# button.net
KiCad netlist of a schematic drawn in EAGLE
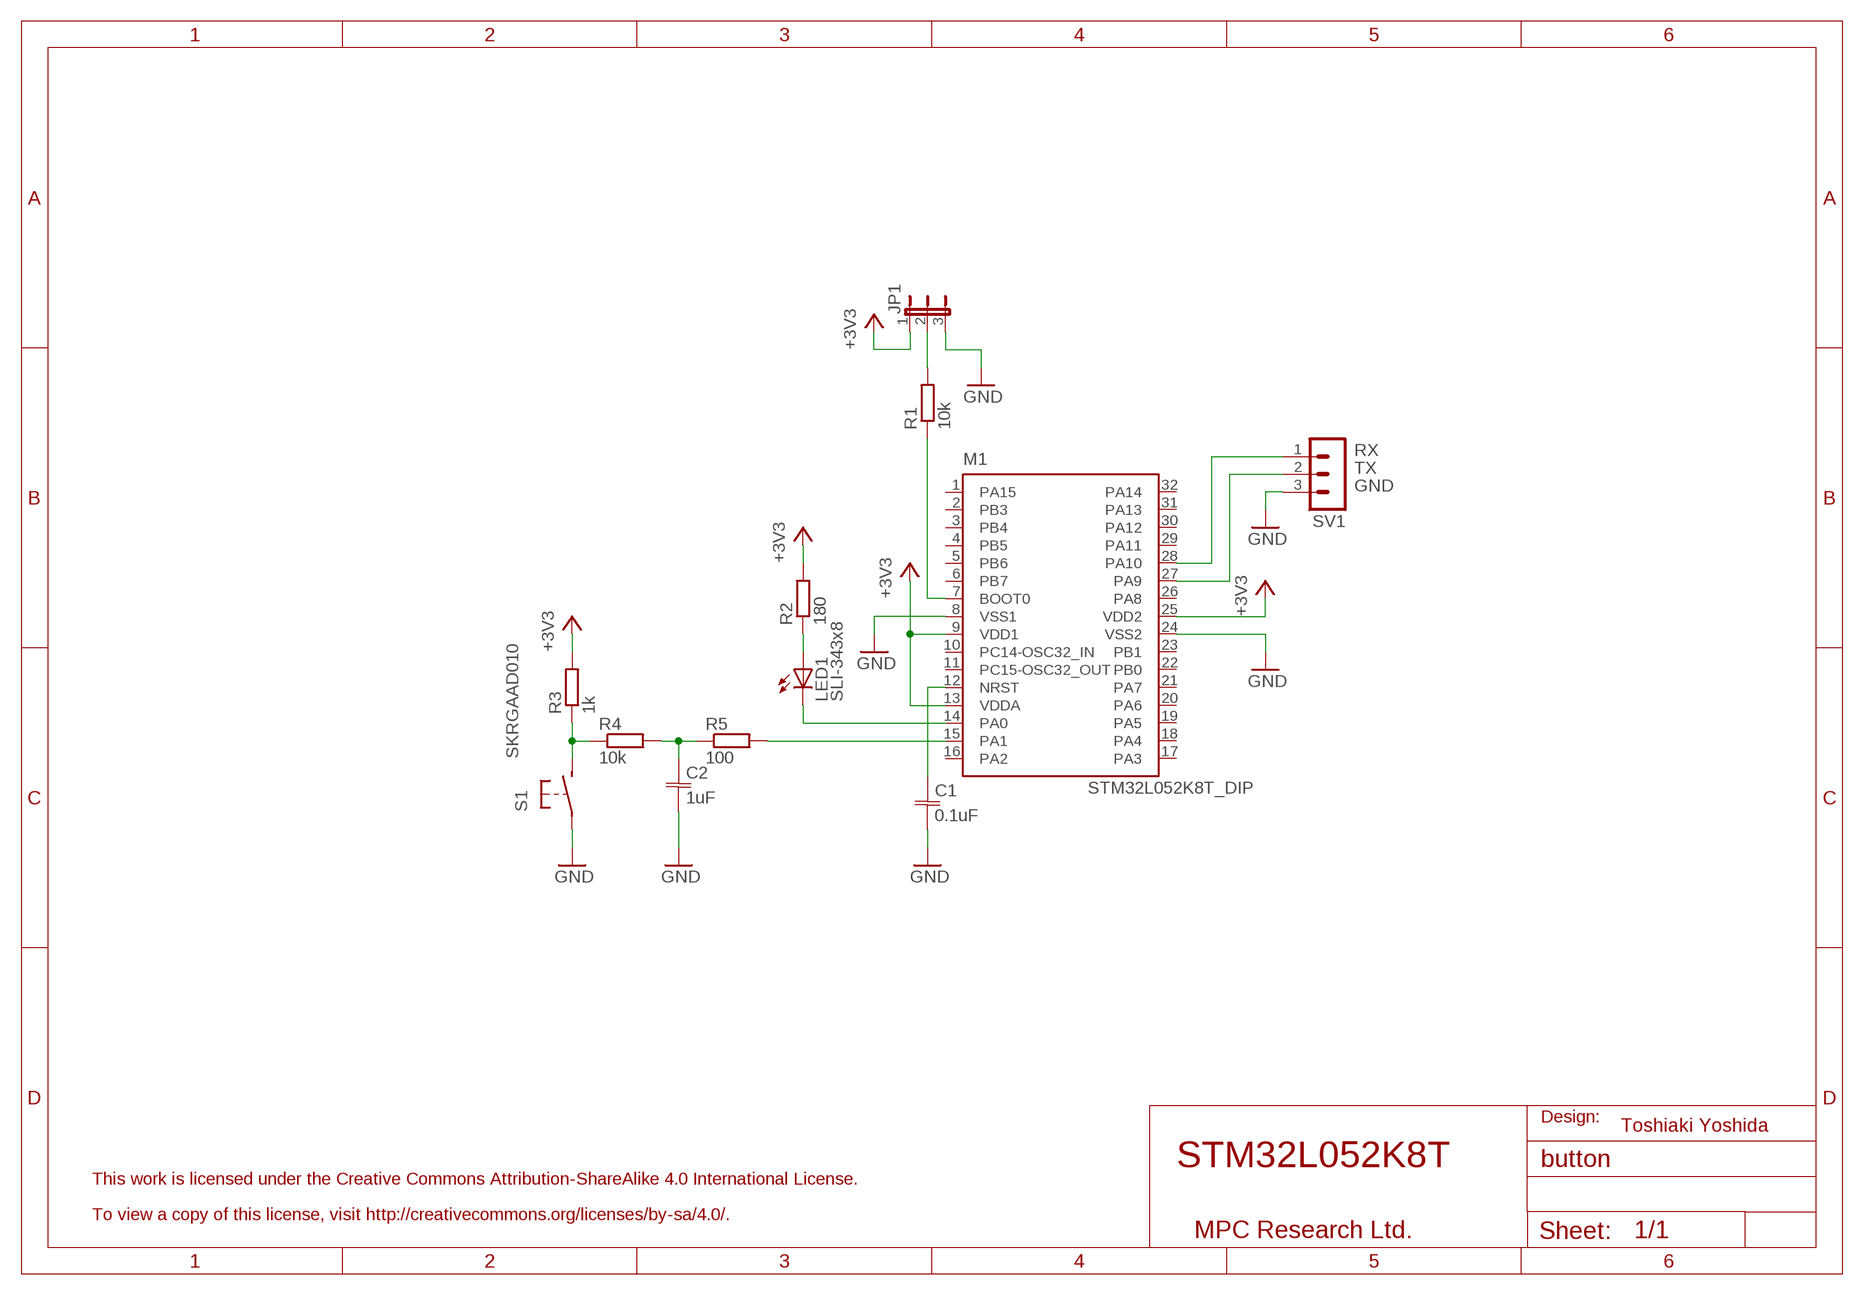
[diagram p0: schematic, sheet 1]

(export (version "E")
  (design (tool "Eeschema 10.0.6"))
  (components
    (comp (ref "C1")
      (value "0.1uF")
      (footprint "eagle-import:C050-024X044")
      (libsource (lib "eagle-import") (part "C-JIS050-024X044"))
    )
    (comp (ref "C2")
      (value "1uF")
      (footprint "eagle-import:C050-024X044")
      (libsource (lib "eagle-import") (part "C-JIS050-024X044"))
    )
    (comp (ref "JP1")
      (value "JP2E")
      (footprint "eagle-import:JP2")
      (libsource (lib "eagle-import") (part "JP2E"))
    )
    (comp (ref "LED1")
      (value "SLI-343x8")
      (footprint "eagle-import:LED3MM")
      (libsource (lib "eagle-import") (part "LED3MM"))
    )
    (comp (ref "M1")
      (value "STM32L052K8T_DIP")
      (footprint "eagle-import:DIP32")
      (libsource (lib "eagle-import") (part "STM32L052K8T_DIP"))
    )
    (comp (ref "R1")
      (value "10k")
      (footprint "eagle-import:0207_2V")
      (libsource (lib "eagle-import") (part "R-EU_0207/2V"))
    )
    (comp (ref "R2")
      (value "180")
      (footprint "eagle-import:0207_2V")
      (libsource (lib "eagle-import") (part "R-EU_0207/2V"))
    )
    (comp (ref "R3")
      (value "1k")
      (footprint "eagle-import:0207_2V")
      (libsource (lib "eagle-import") (part "R-EU_0207/2V"))
    )
    (comp (ref "R4")
      (value "10k")
      (footprint "eagle-import:0207_2V")
      (libsource (lib "eagle-import") (part "R-EU_0207/2V"))
    )
    (comp (ref "R5")
      (value "100")
      (footprint "eagle-import:0207_2V")
      (libsource (lib "eagle-import") (part "R-EU_0207/2V"))
    )
    (comp (ref "S1")
      (value "SKRGAAD010")
      (footprint "eagle-import:SKRG")
      (libsource (lib "eagle-import") (part "SKRGAAD010"))
    )
    (comp (ref "SV1")
      (value "MA03-1")
      (footprint "eagle-import:MA03-1")
      (libsource (lib "eagle-import") (part "MA03-1"))
    )
  )
  (nets
    (net (code "1") (name "+3V3") (class "Default")
      (node (ref "JP1") (pin "1") (pinfunction "1_1") (pintype "passive"))
      (node (ref "M1") (pin "13") (pinfunction "VDDA_13") (pintype "power_in"))
      (node (ref "M1") (pin "25") (pinfunction "VDD2_25") (pintype "bidirectional"))
      (node (ref "M1") (pin "9") (pinfunction "VDD1_9") (pintype "power_in"))
      (node (ref "R2") (pin "2") (pinfunction "2_2") (pintype "passive"))
      (node (ref "R3") (pin "2") (pinfunction "2_2") (pintype "passive"))
    )
    (net (code "2") (name "GND") (class "Default")
      (node (ref "C1") (pin "2") (pinfunction "2_2") (pintype "passive"))
      (node (ref "C2") (pin "2") (pinfunction "2_2") (pintype "passive"))
      (node (ref "JP1") (pin "3") (pinfunction "3_3") (pintype "passive"))
      (node (ref "M1") (pin "24") (pinfunction "VSS2_24") (pintype "power_in"))
      (node (ref "M1") (pin "8") (pinfunction "VSS1_8") (pintype "power_in"))
      (node (ref "S1") (pin "P$1") (pinfunction "1_P$1") (pintype "passive"))
      (node (ref "SV1") (pin "3") (pinfunction "3_3") (pintype "passive"))
    )
    (net (code "3") (name "Net-(C2-Pad1)") (class "Default")
      (node (ref "C2") (pin "1") (pinfunction "1_1") (pintype "passive"))
      (node (ref "R4") (pin "2") (pinfunction "2_2") (pintype "passive"))
      (node (ref "R5") (pin "1") (pinfunction "1_1") (pintype "passive"))
    )
    (net (code "4") (name "Net-(JP1-Pad2)") (class "Default")
      (node (ref "JP1") (pin "2") (pinfunction "2_2") (pintype "passive"))
      (node (ref "R1") (pin "2") (pinfunction "2_2") (pintype "passive"))
    )
    (net (code "5") (name "Net-(LED1-C)") (class "Default")
      (node (ref "LED1") (pin "K") (pinfunction "C_K") (pintype "passive"))
      (node (ref "M1") (pin "14") (pinfunction "PA0_14") (pintype "bidirectional"))
    )
    (net (code "6") (name "Net-(LED1-PadA)") (class "Default")
      (node (ref "LED1") (pin "A") (pinfunction "A_A") (pintype "passive"))
      (node (ref "R2") (pin "1") (pinfunction "1_1") (pintype "passive"))
    )
    (net (code "7") (name "Net-(M1-BOOT0)") (class "Default")
      (node (ref "M1") (pin "7") (pinfunction "BOOT0_7") (pintype "bidirectional"))
      (node (ref "R1") (pin "1") (pinfunction "1_1") (pintype "passive"))
    )
    (net (code "8") (name "Net-(M1-NRST)") (class "Default")
      (node (ref "C1") (pin "1") (pinfunction "1_1") (pintype "passive"))
      (node (ref "M1") (pin "12") (pinfunction "NRST_12") (pintype "bidirectional"))
    )
    (net (code "9") (name "Net-(M1-PA1)") (class "Default")
      (node (ref "M1") (pin "15") (pinfunction "PA1_15") (pintype "bidirectional"))
      (node (ref "R5") (pin "2") (pinfunction "2_2") (pintype "passive"))
    )
    (net (code "10") (name "Net-(M1-PA9)") (class "Default")
      (node (ref "M1") (pin "27") (pinfunction "PA9_27") (pintype "bidirectional"))
      (node (ref "SV1") (pin "2") (pinfunction "2_2") (pintype "passive"))
    )
    (net (code "11") (name "Net-(M1-PA10)") (class "Default")
      (node (ref "M1") (pin "28") (pinfunction "PA10_28") (pintype "bidirectional"))
      (node (ref "SV1") (pin "1") (pinfunction "1_1") (pintype "passive"))
    )
    (net (code "12") (name "Net-(S1-2)") (class "Default")
      (node (ref "R3") (pin "1") (pinfunction "1_1") (pintype "passive"))
      (node (ref "R4") (pin "1") (pinfunction "1_1") (pintype "passive"))
      (node (ref "S1") (pin "P$2") (pinfunction "2_P$2") (pintype "passive"))
    )
    (net (code "13") (name "unconnected-(M1-PA2-Pad16)") (class "Default")
      (node (ref "M1") (pin "16") (pinfunction "PA2_16") (pintype "bidirectional"))
    )
    (net (code "14") (name "unconnected-(M1-PA3-Pad17)") (class "Default")
      (node (ref "M1") (pin "17") (pinfunction "PA3_17") (pintype "bidirectional"))
    )
    (net (code "15") (name "unconnected-(M1-PA4-Pad18)") (class "Default")
      (node (ref "M1") (pin "18") (pinfunction "PA4_18") (pintype "bidirectional"))
    )
    (net (code "16") (name "unconnected-(M1-PA5-Pad19)") (class "Default")
      (node (ref "M1") (pin "19") (pinfunction "PA5_19") (pintype "bidirectional"))
    )
    (net (code "17") (name "unconnected-(M1-PA6-Pad20)") (class "Default")
      (node (ref "M1") (pin "20") (pinfunction "PA6_20") (pintype "bidirectional"))
    )
    (net (code "18") (name "unconnected-(M1-PA7-Pad21)") (class "Default")
      (node (ref "M1") (pin "21") (pinfunction "PA7_21") (pintype "bidirectional"))
    )
    (net (code "19") (name "unconnected-(M1-PA8-Pad26)") (class "Default")
      (node (ref "M1") (pin "26") (pinfunction "PA8_26") (pintype "bidirectional"))
    )
    (net (code "20") (name "unconnected-(M1-PA11-Pad29)") (class "Default")
      (node (ref "M1") (pin "29") (pinfunction "PA11_29") (pintype "bidirectional"))
    )
    (net (code "21") (name "unconnected-(M1-PA12-Pad30)") (class "Default")
      (node (ref "M1") (pin "30") (pinfunction "PA12_30") (pintype "bidirectional"))
    )
    (net (code "22") (name "unconnected-(M1-PA13-Pad31)") (class "Default")
      (node (ref "M1") (pin "31") (pinfunction "PA13_31") (pintype "bidirectional"))
    )
    (net (code "23") (name "unconnected-(M1-PA14-Pad32)") (class "Default")
      (node (ref "M1") (pin "32") (pinfunction "PA14_32") (pintype "bidirectional"))
    )
    (net (code "24") (name "unconnected-(M1-PA15-Pad1)") (class "Default")
      (node (ref "M1") (pin "1") (pinfunction "PA15_1") (pintype "bidirectional"))
    )
    (net (code "25") (name "unconnected-(M1-PB0-Pad22)") (class "Default")
      (node (ref "M1") (pin "22") (pinfunction "PB0_22") (pintype "bidirectional"))
    )
    (net (code "26") (name "unconnected-(M1-PB1-Pad23)") (class "Default")
      (node (ref "M1") (pin "23") (pinfunction "PB1_23") (pintype "bidirectional"))
    )
    (net (code "27") (name "unconnected-(M1-PB3-Pad2)") (class "Default")
      (node (ref "M1") (pin "2") (pinfunction "PB3_2") (pintype "bidirectional"))
    )
    (net (code "28") (name "unconnected-(M1-PB4-Pad3)") (class "Default")
      (node (ref "M1") (pin "3") (pinfunction "PB4_3") (pintype "bidirectional"))
    )
    (net (code "29") (name "unconnected-(M1-PB5-Pad4)") (class "Default")
      (node (ref "M1") (pin "4") (pinfunction "PB5_4") (pintype "bidirectional"))
    )
    (net (code "30") (name "unconnected-(M1-PB6-Pad5)") (class "Default")
      (node (ref "M1") (pin "5") (pinfunction "PB6_5") (pintype "bidirectional"))
    )
    (net (code "31") (name "unconnected-(M1-PB7-Pad6)") (class "Default")
      (node (ref "M1") (pin "6") (pinfunction "PB7_6") (pintype "bidirectional"))
    )
    (net (code "32") (name "unconnected-(M1-PC14-OSC32_IN-Pad10)") (class "Default")
      (node (ref "M1") (pin "10") (pinfunction "PC14-OSC32_IN_10") (pintype "bidirectional"))
    )
    (net (code "33") (name "unconnected-(M1-PC15-OSC32_OUT-Pad11)") (class "Default")
      (node (ref "M1") (pin "11") (pinfunction "PC15-OSC32_OUT_11") (pintype "bidirectional"))
    )
  )
)
